# Motor_Driver.net
KiCad netlist of a schematic drawn in Altium Designer
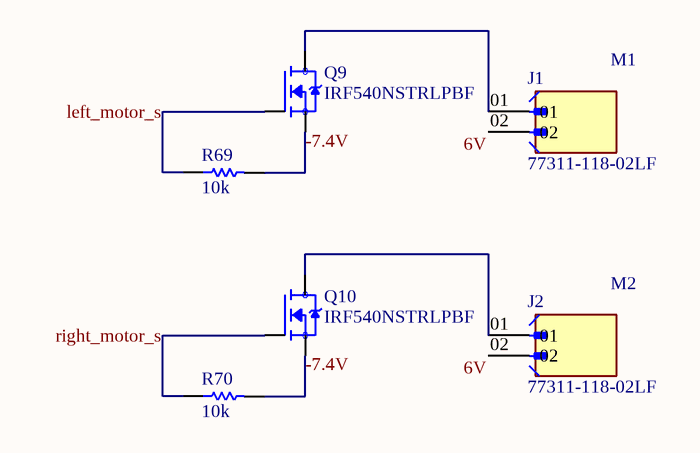
[diagram p0: Motor_Driver.SchDoc]

(export (version "E")
  (design (tool "Eeschema 10.0.6"))
  (components
    (comp (ref "J1")
      (value "77311-118-02LF")
      (footprint "AMPHENOL_77311-118-02LF")
      (fields (field (name "MF") "Amphenol ICC"))
      (libsource (lib "2 pin connector") (part "77311-118-02LF"))
    )
    (comp (ref "J2")
      (value "77311-118-02LF")
      (footprint "AMPHENOL_77311-118-02LF")
      (fields (field (name "MF") "Amphenol ICC"))
      (libsource (lib "2 pin connector") (part "77311-118-02LF"))
    )
    (comp (ref "Q9")
      (value "IRF540NSTRLPBF")
      (footprint "TRANS_IRF540NSTRLPBF")
      (fields (field (name "MF") "Infineon"))
      (libsource (lib "Mosfet") (part "IRF540NSTRLPBF"))
    )
    (comp (ref "Q10")
      (value "IRF540NSTRLPBF")
      (footprint "TRANS_IRF540NSTRLPBF")
      (fields (field (name "MF") "Infineon"))
      (libsource (lib "Mosfet") (part "IRF540NSTRLPBF"))
    )
    (comp (ref "R69")
      (value "10k")
      (footprint "RESC2013X60X35NL10T20")
      (fields (field (name "MANUFACTURER") "Yageo"))
      (libsource (lib "Resistors") (part "10k"))
    )
    (comp (ref "R70")
      (value "10k")
      (footprint "RESC2013X60X35NL10T20")
      (fields (field (name "MANUFACTURER") "Yageo"))
      (libsource (lib "Resistors") (part "10k"))
    )
  )
  (nets
    (net (code "1") (name "/-7.4V") (class "Default")
      (node (ref "Q10") (pin "3") (pinfunction "S_3") (pintype "passive"))
      (node (ref "Q9") (pin "3") (pinfunction "S_3") (pintype "passive"))
      (node (ref "R69") (pin "2") (pinfunction "2_2") (pintype "passive"))
      (node (ref "R70") (pin "2") (pinfunction "2_2") (pintype "passive"))
    )
    (net (code "2") (name "/6V") (class "Default")
      (node (ref "J1") (pin "02") (pinfunction "02_02") (pintype "passive"))
      (node (ref "J2") (pin "02") (pinfunction "02_02") (pintype "passive"))
    )
    (net (code "3") (name "/left_motor_s") (class "Default")
      (node (ref "Q9") (pin "1") (pinfunction "G_1") (pintype "passive"))
      (node (ref "R69") (pin "1") (pinfunction "1_1") (pintype "passive"))
    )
    (net (code "4") (name "/right_motor_s") (class "Default")
      (node (ref "Q10") (pin "1") (pinfunction "G_1") (pintype "passive"))
      (node (ref "R70") (pin "1") (pinfunction "1_1") (pintype "passive"))
    )
    (net (code "5") (name "Net-(Q9-D)") (class "Default")
      (node (ref "J1") (pin "01") (pinfunction "01_01") (pintype "passive"))
      (node (ref "Q9") (pin "2") (pinfunction "D_2") (pintype "passive"))
    )
    (net (code "6") (name "Net-(Q10-D)") (class "Default")
      (node (ref "J2") (pin "01") (pinfunction "01_01") (pintype "passive"))
      (node (ref "Q10") (pin "2") (pinfunction "D_2") (pintype "passive"))
    )
  )
)
